# gatedriver_trafo_sma_compact.net
KiCad netlist of a schematic drawn in EAGLE
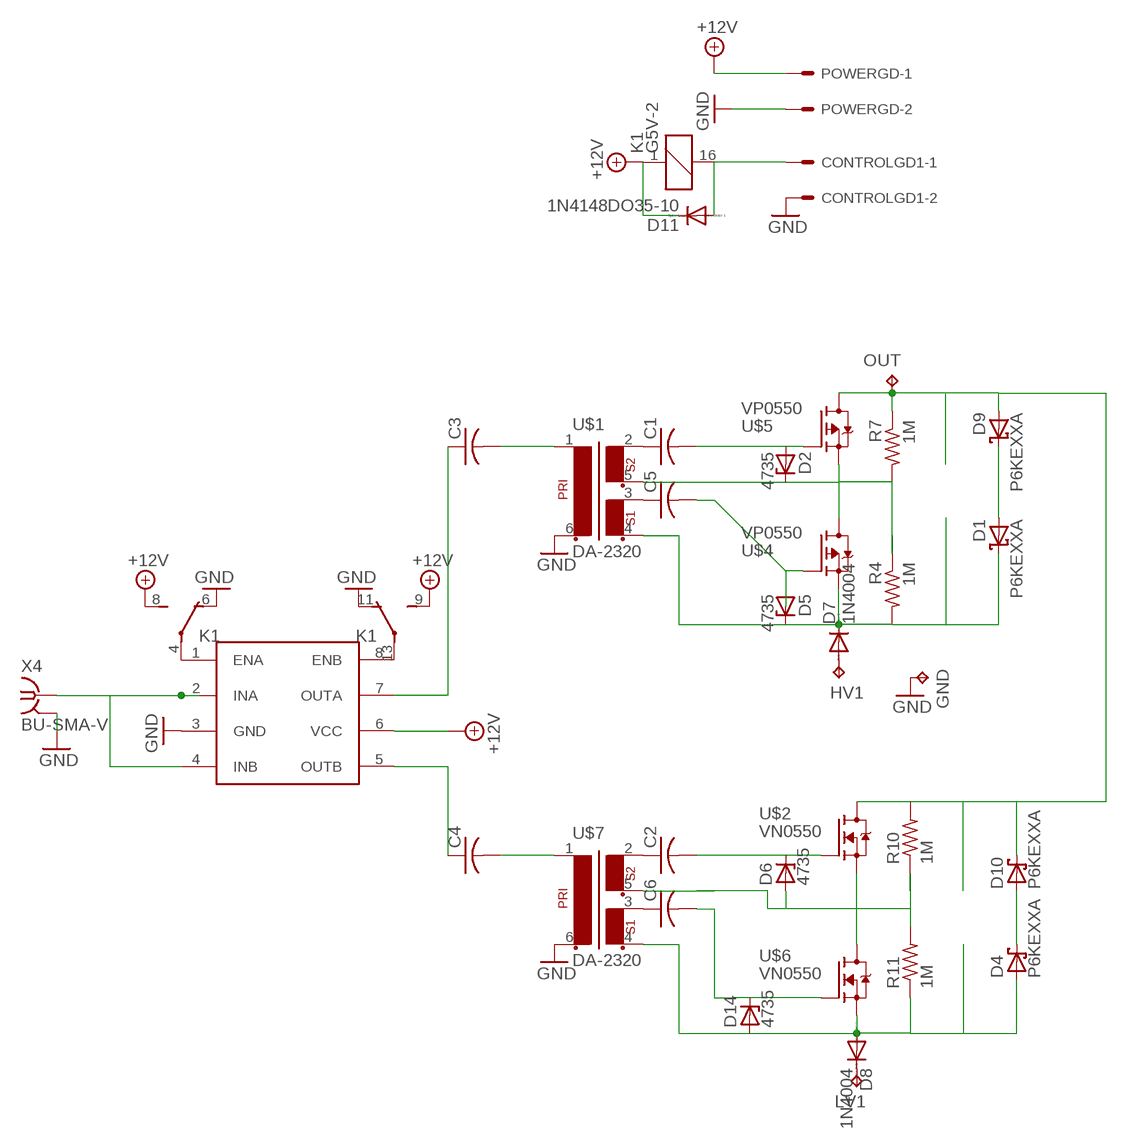
[diagram p0: schematic, sheet 1]

(export (version "E")
  (design (tool "Eeschema 10.0.6"))
  (components
    (comp (ref "C1")
      (value "C-US050-055X075")
      (footprint "eagle-import:C050-055X075")
      (libsource (lib "eagle-import") (part "C-US050-055X075"))
    )
    (comp (ref "C2")
      (value "C-US050-055X075")
      (footprint "eagle-import:C050-055X075")
      (libsource (lib "eagle-import") (part "C-US050-055X075"))
    )
    (comp (ref "C3")
      (value "C-US050-055X075")
      (footprint "eagle-import:C050-055X075")
      (libsource (lib "eagle-import") (part "C-US050-055X075"))
    )
    (comp (ref "C4")
      (value "C-US050-055X075")
      (footprint "eagle-import:C050-055X075")
      (libsource (lib "eagle-import") (part "C-US050-055X075"))
    )
    (comp (ref "C5")
      (value "C-US050-055X075")
      (footprint "eagle-import:C050-055X075")
      (libsource (lib "eagle-import") (part "C-US050-055X075"))
    )
    (comp (ref "C6")
      (value "C-US050-055X075")
      (footprint "eagle-import:C050-055X075")
      (libsource (lib "eagle-import") (part "C-US050-055X075"))
    )
    (comp (ref "CONTROLGD1")
      (value "KK-156-2")
      (footprint "eagle-import:KK-156-2")
      (libsource (lib "eagle-import") (part "KK-156-2"))
    )
    (comp (ref "D1")
      (value "P6KEXXA")
      (footprint "eagle-import:C1702-15")
      (libsource (lib "eagle-import") (part "P6KEXXA"))
    )
    (comp (ref "D2")
      (value "4735")
      (footprint "eagle-import:ZDIO-10")
      (libsource (lib "eagle-import") (part "ZENER-DIODEZD-10"))
    )
    (comp (ref "D4")
      (value "P6KEXXA")
      (footprint "eagle-import:C1702-15")
      (libsource (lib "eagle-import") (part "P6KEXXA"))
    )
    (comp (ref "D5")
      (value "4735")
      (footprint "eagle-import:ZDIO-10")
      (libsource (lib "eagle-import") (part "ZENER-DIODEZD-10"))
    )
    (comp (ref "D6")
      (value "4735")
      (footprint "eagle-import:ZDIO-10")
      (libsource (lib "eagle-import") (part "ZENER-DIODEZD-10"))
    )
    (comp (ref "D7")
      (value "1N4004")
      (footprint "eagle-import:DO41-10")
      (libsource (lib "eagle-import") (part "1N4004"))
    )
    (comp (ref "D8")
      (value "1N4004")
      (footprint "eagle-import:DO41-10")
      (libsource (lib "eagle-import") (part "1N4004"))
    )
    (comp (ref "D9")
      (value "P6KEXXA")
      (footprint "eagle-import:C1702-15")
      (libsource (lib "eagle-import") (part "P6KEXXA"))
    )
    (comp (ref "D10")
      (value "P6KEXXA")
      (footprint "eagle-import:C1702-15")
      (libsource (lib "eagle-import") (part "P6KEXXA"))
    )
    (comp (ref "D11")
      (value "1N4148DO35-10")
      (footprint "eagle-import:DO35-10")
      (libsource (lib "eagle-import") (part "1N4148DO35-10"))
    )
    (comp (ref "D14")
      (value "4735")
      (footprint "eagle-import:ZDIO-10")
      (libsource (lib "eagle-import") (part "ZENER-DIODEZD-10"))
    )
    (comp (ref "GND")
      (value "TPPAD1-20Y")
      (footprint "eagle-import:P1-20Y")
      (libsource (lib "eagle-import") (part "TPPAD1-20Y"))
    )
    (comp (ref "HV1")
      (value "TPPAD1-20Y")
      (footprint "eagle-import:P1-20Y")
      (libsource (lib "eagle-import") (part "TPPAD1-20Y"))
    )
    (comp (ref "K1")
      (value "G5V-2")
      (footprint "eagle-import:G5V-2")
      (fields (field (name "MPN") "G5V-2 5DC"))
      (libsource (lib "eagle-import") (part "G5V-2"))
    )
    (comp (ref "LV1")
      (value "TPPAD1-20Y")
      (footprint "eagle-import:P1-20Y")
      (libsource (lib "eagle-import") (part "TPPAD1-20Y"))
    )
    (comp (ref "OUT")
      (value "TPPAD1-20Y")
      (footprint "eagle-import:P1-20Y")
      (libsource (lib "eagle-import") (part "TPPAD1-20Y"))
    )
    (comp (ref "POWERGD")
      (value "KK-156-2")
      (footprint "eagle-import:KK-156-2")
      (libsource (lib "eagle-import") (part "KK-156-2"))
    )
    (comp (ref "R4")
      (value "1M")
      (footprint "eagle-import:0207_12")
      (libsource (lib "eagle-import") (part "R-US_0207/12"))
    )
    (comp (ref "R7")
      (value "1M")
      (footprint "eagle-import:0207_12")
      (libsource (lib "eagle-import") (part "R-US_0207/12"))
    )
    (comp (ref "R10")
      (value "1M")
      (footprint "eagle-import:0207_12")
      (libsource (lib "eagle-import") (part "R-US_0207/12"))
    )
    (comp (ref "R11")
      (value "1M")
      (footprint "eagle-import:0207_12")
      (libsource (lib "eagle-import") (part "R-US_0207/12"))
    )
    (comp (ref "U$1")
      (value "DA-2320")
      (footprint "eagle-import:DIL06")
      (libsource (lib "eagle-import") (part "DA-2320"))
    )
    (comp (ref "U$2")
      (value "VN0550")
      (footprint "eagle-import:TO92-")
      (libsource (lib "eagle-import") (part "VN0550"))
    )
    (comp (ref "U$3")
      (value "UCC27425")
      (footprint "eagle-import:DIL08")
      (libsource (lib "eagle-import") (part "UCC27425"))
    )
    (comp (ref "U$4")
      (value "VP0550")
      (footprint "eagle-import:TO92-")
      (libsource (lib "eagle-import") (part "VP0550"))
    )
    (comp (ref "U$5")
      (value "VP0550")
      (footprint "eagle-import:TO92-")
      (libsource (lib "eagle-import") (part "VP0550"))
    )
    (comp (ref "U$6")
      (value "VN0550")
      (footprint "eagle-import:TO92-")
      (libsource (lib "eagle-import") (part "VN0550"))
    )
    (comp (ref "U$7")
      (value "DA-2320")
      (footprint "eagle-import:DIL06")
      (libsource (lib "eagle-import") (part "DA-2320"))
    )
    (comp (ref "X4")
      (value "BU-SMA-V")
      (footprint "eagle-import:BU-SMA-V")
      (libsource (lib "eagle-import") (part "BU-SMA-V"))
    )
  )
  (nets
    (net (code "1") (name "+12V") (class "Default")
      (node (ref "D11") (pin "C") (pinfunction "C_C") (pintype "passive"))
      (node (ref "K1") (pin "1") (pinfunction "1_1") (pintype "passive"))
      (node (ref "K1") (pin "8") (pinfunction "S_8") (pintype "passive"))
      (node (ref "K1") (pin "9") (pinfunction "S_9") (pintype "passive"))
      (node (ref "POWERGD") (pin "1") (pinfunction "S_1") (pintype "passive"))
      (node (ref "U$3") (pin "6") (pinfunction "VCC_6") (pintype "bidirectional"))
    )
    (net (code "2") (name "/N$17") (class "Default")
      (node (ref "D1") (pin "C") (pinfunction "C_C") (pintype "passive"))
      (node (ref "D5") (pin "C") (pinfunction "C_C") (pintype "passive"))
      (node (ref "D7") (pin "C") (pinfunction "C_C") (pintype "passive"))
      (node (ref "R4") (pin "2") (pinfunction "2_2") (pintype "passive"))
      (node (ref "U$1") (pin "4") (pinfunction "3_4") (pintype "passive"))
      (node (ref "U$4") (pin "3") (pinfunction "S_3") (pintype "passive"))
    )
    (net (code "3") (name "/N$25") (class "Default")
      (node (ref "C2") (pin "2") (pinfunction "2_2") (pintype "passive"))
      (node (ref "D6") (pin "C") (pinfunction "C_C") (pintype "passive"))
      (node (ref "U$2") (pin "2") (pinfunction "G_2") (pintype "passive"))
    )
    (net (code "4") (name "GND") (class "Default")
      (node (ref "CONTROLGD1") (pin "2") (pinfunction "S_2") (pintype "passive"))
      (node (ref "GND") (pin "TP") (pinfunction "TP_TP") (pintype "input"))
      (node (ref "K1") (pin "11") (pinfunction "O_11") (pintype "passive"))
      (node (ref "K1") (pin "6") (pinfunction "O_6") (pintype "passive"))
      (node (ref "POWERGD") (pin "2") (pinfunction "S_2") (pintype "passive"))
      (node (ref "U$1") (pin "6") (pinfunction "2_6") (pintype "passive"))
      (node (ref "U$3") (pin "3") (pinfunction "GND_3") (pintype "bidirectional"))
      (node (ref "U$7") (pin "6") (pinfunction "2_6") (pintype "passive"))
      (node (ref "X4") (pin "2") (pinfunction "2_2") (pintype "passive"))
      (node (ref "X4") (pin "3") (pinfunction "2_3") (pintype "passive"))
      (node (ref "X4") (pin "4") (pinfunction "2_4") (pintype "passive"))
      (node (ref "X4") (pin "5") (pinfunction "2_5") (pintype "passive"))
    )
    (net (code "5") (name "Net-(C3-Pad2)") (class "Default")
      (node (ref "C3") (pin "2") (pinfunction "2_2") (pintype "passive"))
      (node (ref "U$1") (pin "1") (pinfunction "1_1") (pintype "passive"))
    )
    (net (code "6") (name "Net-(C4-Pad2)") (class "Default")
      (node (ref "C4") (pin "2") (pinfunction "2_2") (pintype "passive"))
      (node (ref "U$7") (pin "1") (pinfunction "1_1") (pintype "passive"))
    )
    (net (code "7") (name "Net-(CONTROLGD1A-S)") (class "Default")
      (node (ref "CONTROLGD1") (pin "1") (pinfunction "S_1") (pintype "passive"))
      (node (ref "D11") (pin "A") (pinfunction "A_A") (pintype "passive"))
      (node (ref "K1") (pin "16") (pinfunction "2_16") (pintype "passive"))
    )
    (net (code "8") (name "Net-(D1-PadA)") (class "Default")
      (node (ref "D1") (pin "A") (pinfunction "A_A") (pintype "passive"))
      (node (ref "D9") (pin "C") (pinfunction "C_C") (pintype "passive"))
    )
    (net (code "9") (name "Net-(D7-PadA)") (class "Default")
      (node (ref "D7") (pin "A") (pinfunction "A_A") (pintype "passive"))
      (node (ref "HV1") (pin "TP") (pinfunction "TP_TP") (pintype "input"))
    )
    (net (code "10") (name "Net-(D8-PadC)") (class "Default")
      (node (ref "D8") (pin "C") (pinfunction "C_C") (pintype "passive"))
      (node (ref "LV1") (pin "TP") (pinfunction "TP_TP") (pintype "input"))
    )
    (net (code "11") (name "Net-(D10-PadA)") (class "Default")
      (node (ref "D10") (pin "A") (pinfunction "A_A") (pintype "passive"))
      (node (ref "D4") (pin "C") (pinfunction "C_C") (pintype "passive"))
    )
    (net (code "12") (name "Net-(K1A-P)") (class "Default")
      (node (ref "K1") (pin "4") (pinfunction "P_4") (pintype "passive"))
      (node (ref "U$3") (pin "1") (pinfunction "ENA_1") (pintype "bidirectional"))
    )
    (net (code "13") (name "Net-(K1B-P)") (class "Default")
      (node (ref "K1") (pin "13") (pinfunction "P_13") (pintype "passive"))
      (node (ref "U$3") (pin "8") (pinfunction "ENB_8") (pintype "bidirectional"))
    )
    (net (code "14") (name "Net-(U$1-4)") (class "Default")
      (node (ref "C5") (pin "1") (pinfunction "1_1") (pintype "passive"))
      (node (ref "U$1") (pin "3") (pinfunction "4_3") (pintype "passive"))
    )
    (net (code "15") (name "Net-(U$1-6)") (class "Default")
      (node (ref "C1") (pin "1") (pinfunction "1_1") (pintype "passive"))
      (node (ref "U$1") (pin "2") (pinfunction "6_2") (pintype "passive"))
    )
    (net (code "16") (name "Net-(U$2-D)") (class "Default")
      (node (ref "D10") (pin "C") (pinfunction "C_C") (pintype "passive"))
      (node (ref "D9") (pin "A") (pinfunction "A_A") (pintype "passive"))
      (node (ref "OUT") (pin "TP") (pinfunction "TP_TP") (pintype "input"))
      (node (ref "R10") (pin "2") (pinfunction "2_2") (pintype "passive"))
      (node (ref "R7") (pin "1") (pinfunction "1_1") (pintype "passive"))
      (node (ref "U$2") (pin "1") (pinfunction "D_1") (pintype "passive"))
      (node (ref "U$5") (pin "1") (pinfunction "D_1") (pintype "passive"))
    )
    (net (code "17") (name "Net-(U$2-S)") (class "Default")
      (node (ref "D6") (pin "A") (pinfunction "A_A") (pintype "passive"))
      (node (ref "R10") (pin "1") (pinfunction "1_1") (pintype "passive"))
      (node (ref "R11") (pin "2") (pinfunction "2_2") (pintype "passive"))
      (node (ref "U$2") (pin "3") (pinfunction "S_3") (pintype "passive"))
      (node (ref "U$6") (pin "1") (pinfunction "D_1") (pintype "passive"))
    )
    (net (code "18") (name "Net-(U$3-INA)") (class "Default")
      (node (ref "U$3") (pin "2") (pinfunction "INA_2") (pintype "bidirectional"))
      (node (ref "U$3") (pin "4") (pinfunction "INB_4") (pintype "bidirectional"))
      (node (ref "X4") (pin "1") (pinfunction "1_1") (pintype "passive"))
    )
    (net (code "19") (name "Net-(U$3-OUTA)") (class "Default")
      (node (ref "C3") (pin "1") (pinfunction "1_1") (pintype "passive"))
      (node (ref "U$3") (pin "7") (pinfunction "OUTA_7") (pintype "bidirectional"))
    )
    (net (code "20") (name "Net-(U$3-OUTB)") (class "Default")
      (node (ref "C4") (pin "1") (pinfunction "1_1") (pintype "passive"))
      (node (ref "U$3") (pin "5") (pinfunction "OUTB_5") (pintype "bidirectional"))
    )
    (net (code "21") (name "Net-(U$4-D)") (class "Default")
      (node (ref "D2") (pin "C") (pinfunction "C_C") (pintype "passive"))
      (node (ref "R4") (pin "1") (pinfunction "1_1") (pintype "passive"))
      (node (ref "R7") (pin "2") (pinfunction "2_2") (pintype "passive"))
      (node (ref "U$1") (pin "5") (pinfunction "5_5") (pintype "passive"))
      (node (ref "U$4") (pin "1") (pinfunction "D_1") (pintype "passive"))
      (node (ref "U$5") (pin "3") (pinfunction "S_3") (pintype "passive"))
    )
    (net (code "22") (name "Net-(U$4-G)") (class "Default")
      (node (ref "C5") (pin "2") (pinfunction "2_2") (pintype "passive"))
      (node (ref "D5") (pin "A") (pinfunction "A_A") (pintype "passive"))
      (node (ref "U$4") (pin "2") (pinfunction "G_2") (pintype "passive"))
    )
    (net (code "23") (name "Net-(U$5-G)") (class "Default")
      (node (ref "C1") (pin "2") (pinfunction "2_2") (pintype "passive"))
      (node (ref "D2") (pin "A") (pinfunction "A_A") (pintype "passive"))
      (node (ref "U$5") (pin "2") (pinfunction "G_2") (pintype "passive"))
    )
    (net (code "24") (name "Net-(U$6-G)") (class "Default")
      (node (ref "C6") (pin "2") (pinfunction "2_2") (pintype "passive"))
      (node (ref "D14") (pin "C") (pinfunction "C_C") (pintype "passive"))
      (node (ref "U$6") (pin "2") (pinfunction "G_2") (pintype "passive"))
    )
    (net (code "25") (name "Net-(U$6-S)") (class "Default")
      (node (ref "D14") (pin "A") (pinfunction "A_A") (pintype "passive"))
      (node (ref "D4") (pin "A") (pinfunction "A_A") (pintype "passive"))
      (node (ref "D8") (pin "A") (pinfunction "A_A") (pintype "passive"))
      (node (ref "R11") (pin "1") (pinfunction "1_1") (pintype "passive"))
      (node (ref "U$6") (pin "3") (pinfunction "S_3") (pintype "passive"))
      (node (ref "U$7") (pin "4") (pinfunction "3_4") (pintype "passive"))
    )
    (net (code "26") (name "Net-(U$7-4)") (class "Default")
      (node (ref "C6") (pin "1") (pinfunction "1_1") (pintype "passive"))
      (node (ref "U$7") (pin "3") (pinfunction "4_3") (pintype "passive"))
    )
    (net (code "27") (name "Net-(U$7-6)") (class "Default")
      (node (ref "C2") (pin "1") (pinfunction "1_1") (pintype "passive"))
      (node (ref "U$7") (pin "2") (pinfunction "6_2") (pintype "passive"))
    )
    (net (code "28") (name "unconnected-(U$7-Pad5)") (class "Default")
      (node (ref "U$7") (pin "5") (pinfunction "5_5") (pintype "passive"))
    )
  )
)
